# E-44_IPS_TX.net
KiCad netlist of a schematic drawn in Altium Designer
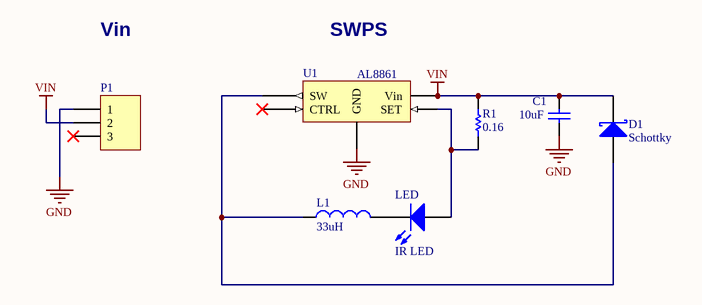
[diagram p0: E-44 IPS TX.SchDoc]

(export (version "E")
  (design (tool "Eeschema 10.0.6"))
  (components
    (comp (ref "C1")
      (value "10uF")
      (footprint "0603 TIGHT")
      (description "Capacitor")
      (fields (field (name "PUBLISHER") "Altium Limited"))
      (libsource (lib "SB_Discrete") (part "Cap"))
    )
    (comp (ref "D1")
      (value "Schottky")
      (footprint "DIODE SOD-123")
      (description "Schottky Diode")
      (fields (field (name "PUBLISHER") "Altium Limited"))
      (libsource (lib "ezrobot") (part "D Schottky"))
    )
    (comp (ref "L1")
      (value "33uH")
      (footprint "IND SMD LRG")
      (description "Inductor")
      (fields (field (name "Comment") "Ferrite") (field (name "PUBLISHER") "Altium Limited"))
      (libsource (lib "Miscellaneous Devices") (part "Inductor"))
    )
    (comp (ref "LED")
      (value "IR LED")
      (footprint "IR LED")
      (libsource (lib "SB_Engineered_Components") (part "IR LED"))
    )
    (comp (ref "P1")
      (value "Header 3")
      (footprint "JST-PH 3-pin SMD")
      (description "Header, 3-Pin")
      (fields (field (name "PUBLISHER") "Altium Limited"))
      (libsource (lib "Miscellaneous Connectors") (part "Header 3"))
    )
    (comp (ref "R1")
      (value "0.16")
      (footprint "0603 tight")
      (description "Resistor")
      (fields (field (name "Comment") "Res1") (field (name "PUBLISHER") "Altium Limited"))
      (libsource (lib "SB_Discrete") (part "Res1"))
    )
    (comp (ref "U1") (value "AL8861") (footprint "SOT-25 new") (libsource (lib "ezrobot") (part "AL8860")))
  )
  (nets
    (net (code "1") (name "GND") (class "Default")
      (node (ref "C1") (pin "1") (pinfunction "1_1") (pintype "passive"))
      (node (ref "P1") (pin "1") (pinfunction "1_1") (pintype "passive"))
      (node (ref "U1") (pin "3") (pinfunction "GND_3") (pintype "power_in"))
    )
    (net (code "2") (name "Net-(D1-A)") (class "Default")
      (node (ref "D1") (pin "1") (pinfunction "A_1") (pintype "passive"))
      (node (ref "L1") (pin "1") (pinfunction "1_1") (pintype "passive"))
      (node (ref "U1") (pin "5") (pinfunction "SW_5") (pintype "output"))
    )
    (net (code "3") (name "Net-(LED-A)") (class "Default")
      (node (ref "LED") (pin "1") (pinfunction "A_1") (pintype "passive"))
      (node (ref "R1") (pin "1") (pinfunction "1_1") (pintype "passive"))
      (node (ref "U1") (pin "1") (pinfunction "SET_1") (pintype "input"))
    )
    (net (code "4") (name "Net-(LED-K)") (class "Default")
      (node (ref "L1") (pin "2") (pinfunction "2_2") (pintype "passive"))
      (node (ref "LED") (pin "2") (pinfunction "K_2") (pintype "passive"))
    )
    (net (code "5") (name "VIN") (class "Default")
      (node (ref "C1") (pin "2") (pinfunction "2_2") (pintype "passive"))
      (node (ref "D1") (pin "2") (pinfunction "K_2") (pintype "passive"))
      (node (ref "P1") (pin "2") (pinfunction "2_2") (pintype "passive"))
      (node (ref "R1") (pin "2") (pinfunction "2_2") (pintype "passive"))
      (node (ref "U1") (pin "2") (pinfunction "Vin_2") (pintype "power_in"))
    )
    (net (code "6") (name "unconnected-(P1-Pad3)") (class "Default")
      (node (ref "P1") (pin "3") (pinfunction "3_3") (pintype "passive+no_connect"))
    )
    (net (code "7") (name "unconnected-(U1-CTRL-Pad4)") (class "Default")
      (node (ref "U1") (pin "4") (pinfunction "CTRL_4") (pintype "input+no_connect"))
    )
  )
)
